# MotorCell.net
KiCad netlist of a schematic drawn in Altium Designer
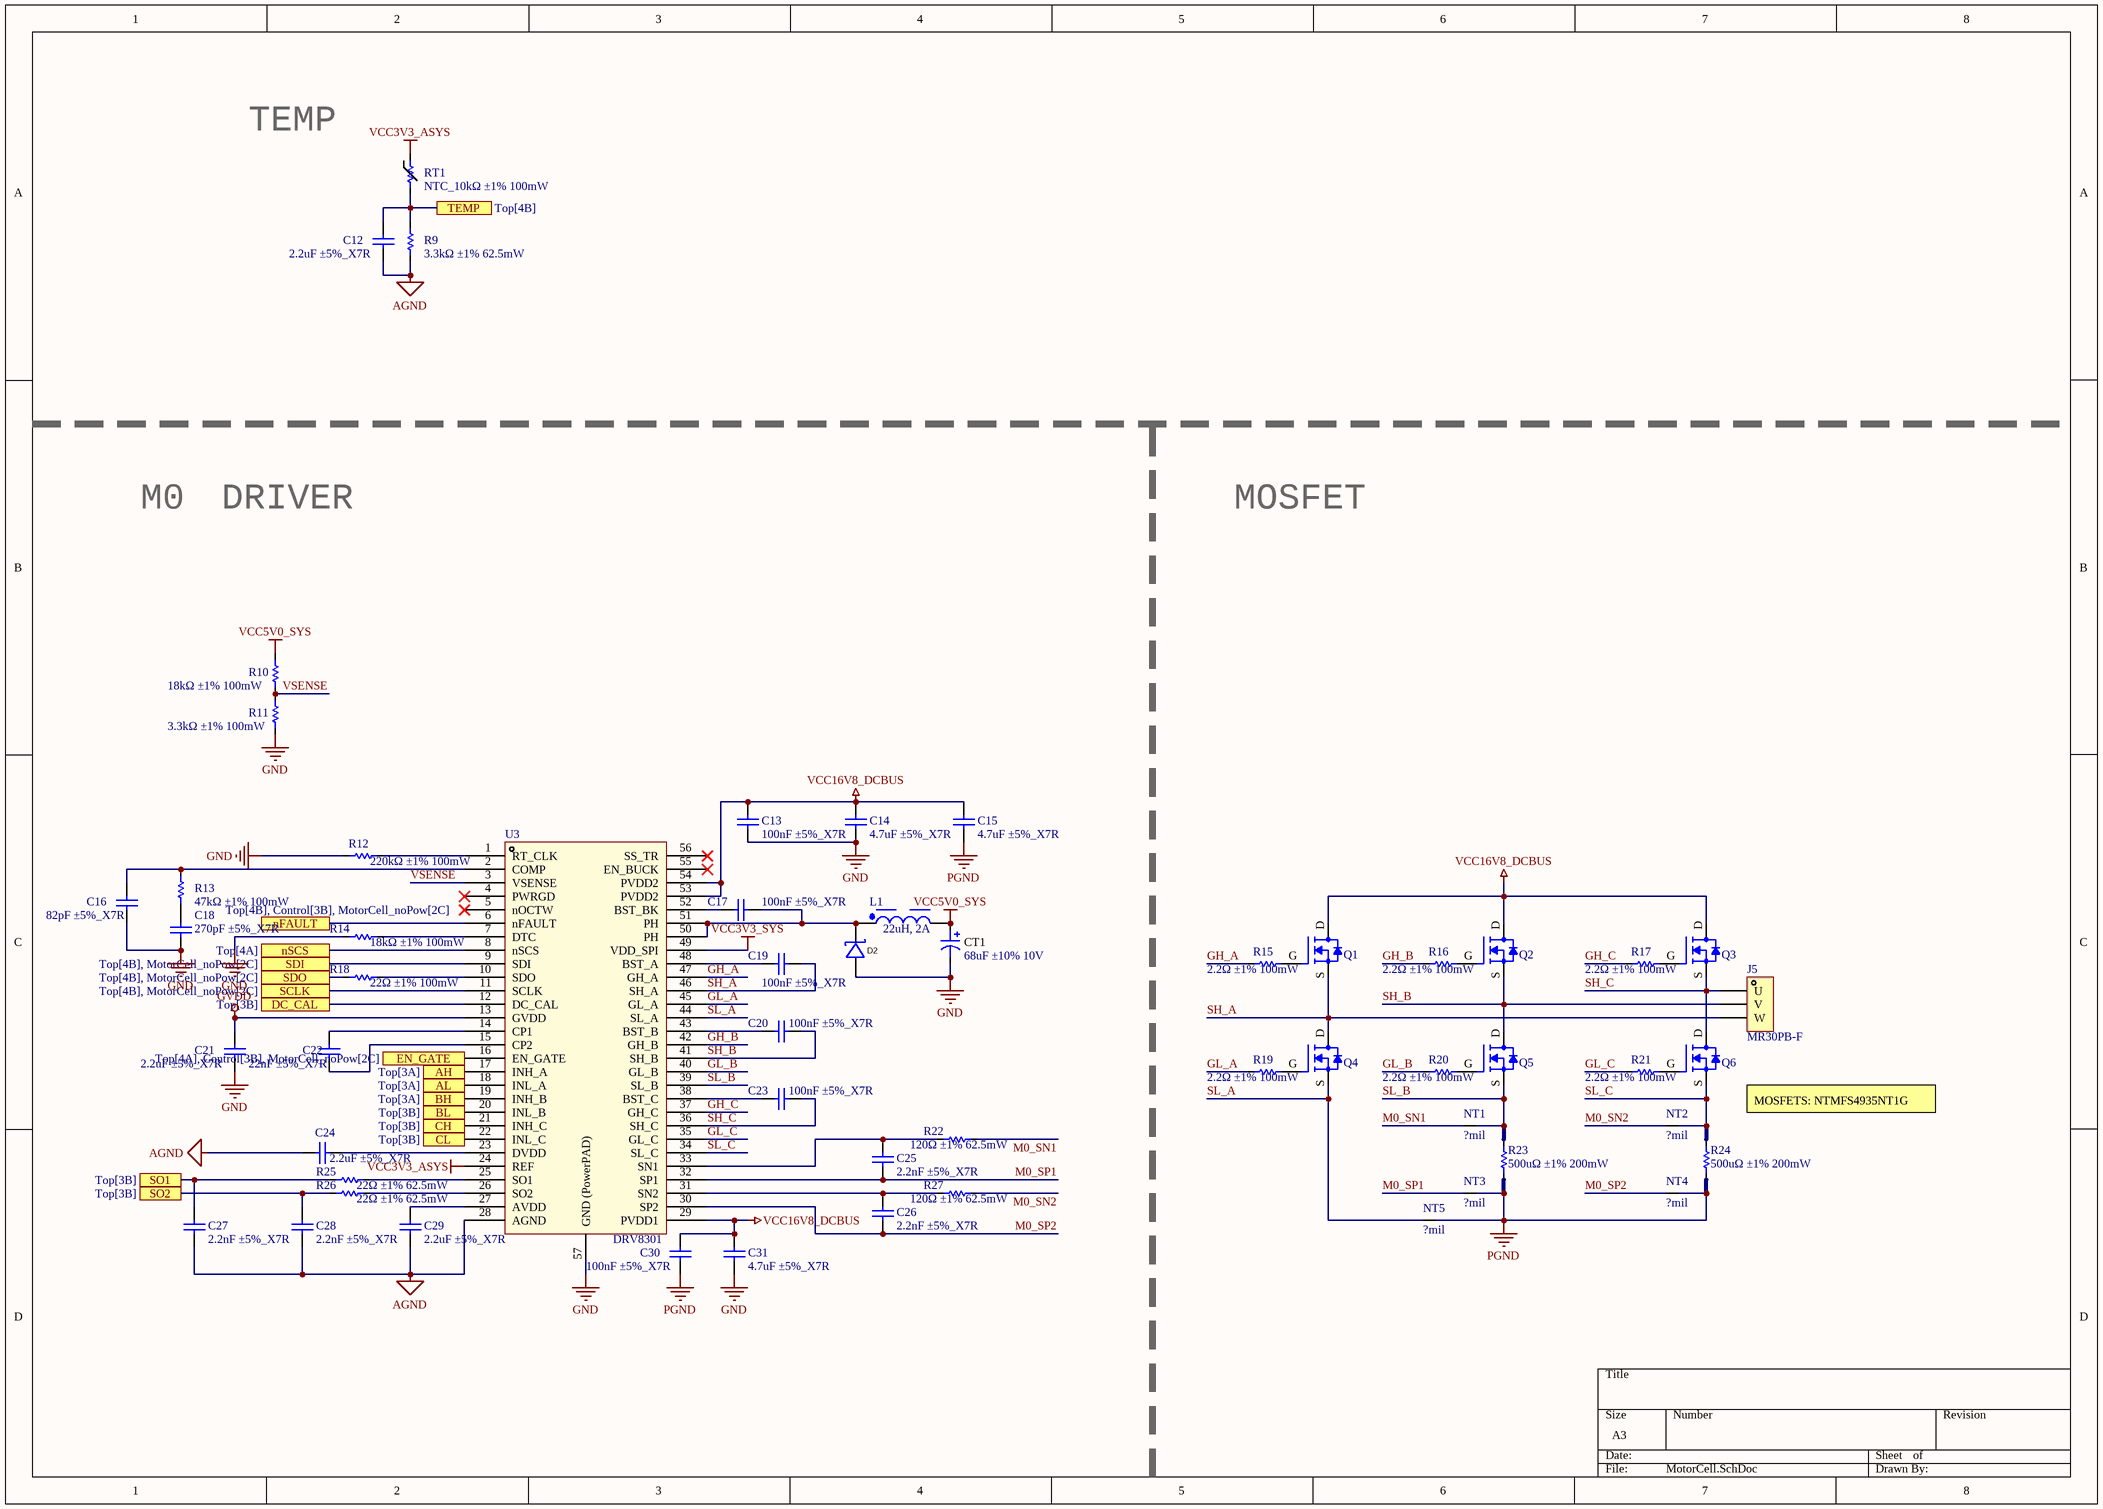
[diagram p0: MotorCell.SchDoc]

(export (version "E")
  (design (tool "Eeschema 10.0.6"))
  (components
    (comp (ref "C12")
      (value "2.2uF ±5%_X7R")
      (footprint "C0402")
      (description "Capacitor")
      (fields (field (name "PUBLISHER") "Altium Limited"))
      (libsource (lib "Component") (part "Cap"))
    )
    (comp (ref "C13")
      (value "100nF ±5%_X7R")
      (footprint "C0402")
      (description "Capacitor")
      (fields (field (name "PUBLISHER") "Altium Limited"))
      (libsource (lib "Component") (part "Cap"))
    )
    (comp (ref "C14")
      (value "4.7uF ±5%_X7R")
      (footprint "C0603")
      (description "Capacitor")
      (fields (field (name "PUBLISHER") "Altium Limited"))
      (libsource (lib "Component") (part "Cap"))
    )
    (comp (ref "C15")
      (value "4.7uF ±5%_X7R")
      (footprint "C0603")
      (description "Capacitor")
      (fields (field (name "PUBLISHER") "Altium Limited"))
      (libsource (lib "Component") (part "Cap"))
    )
    (comp (ref "C16")
      (value "82pF ±5%_X7R")
      (footprint "C0402")
      (description "Capacitor")
      (fields (field (name "PUBLISHER") "Altium Limited"))
      (libsource (lib "Component") (part "Cap"))
    )
    (comp (ref "C17")
      (value "100nF ±5%_X7R")
      (footprint "C0402")
      (description "Capacitor")
      (fields (field (name "PUBLISHER") "Altium Limited"))
      (libsource (lib "Component") (part "Cap"))
    )
    (comp (ref "C18")
      (value "270pF ±5%_X7R")
      (footprint "C0402")
      (description "Capacitor")
      (fields (field (name "PUBLISHER") "Altium Limited"))
      (libsource (lib "Component") (part "Cap"))
    )
    (comp (ref "C19")
      (value "100nF ±5%_X7R")
      (footprint "C0402")
      (description "Capacitor")
      (fields (field (name "PUBLISHER") "Altium Limited"))
      (libsource (lib "Component") (part "Cap"))
    )
    (comp (ref "C20")
      (value "100nF ±5%_X7R")
      (footprint "C0402")
      (description "Capacitor")
      (fields (field (name "PUBLISHER") "Altium Limited"))
      (libsource (lib "Component") (part "Cap"))
    )
    (comp (ref "C21")
      (value "2.2uF ±5%_X7R")
      (footprint "C0603")
      (description "Capacitor")
      (fields (field (name "PUBLISHER") "Altium Limited"))
      (libsource (lib "Component") (part "Cap"))
    )
    (comp (ref "C22")
      (value "22nF ±5%_X7R")
      (footprint "C0603")
      (description "Capacitor")
      (fields (field (name "PUBLISHER") "Altium Limited"))
      (libsource (lib "Component") (part "Cap"))
    )
    (comp (ref "C23")
      (value "100nF ±5%_X7R")
      (footprint "C0402")
      (description "Capacitor")
      (fields (field (name "PUBLISHER") "Altium Limited"))
      (libsource (lib "Component") (part "Cap"))
    )
    (comp (ref "C24")
      (value "2.2uF ±5%_X7R")
      (footprint "C0603")
      (description "Capacitor")
      (fields (field (name "PUBLISHER") "Altium Limited"))
      (libsource (lib "Component") (part "Cap"))
    )
    (comp (ref "C25")
      (value "2.2nF ±5%_X7R")
      (footprint "C0402")
      (description "Capacitor")
      (fields (field (name "PUBLISHER") "Altium Limited"))
      (libsource (lib "Component") (part "Cap"))
    )
    (comp (ref "C26")
      (value "2.2nF ±5%_X7R")
      (footprint "C0402")
      (description "Capacitor")
      (fields (field (name "PUBLISHER") "Altium Limited"))
      (libsource (lib "Component") (part "Cap"))
    )
    (comp (ref "C27")
      (value "2.2nF ±5%_X7R")
      (footprint "C0402")
      (description "Capacitor")
      (fields (field (name "PUBLISHER") "Altium Limited"))
      (libsource (lib "Component") (part "Cap"))
    )
    (comp (ref "C28")
      (value "2.2nF ±5%_X7R")
      (footprint "C0402")
      (description "Capacitor")
      (fields (field (name "PUBLISHER") "Altium Limited"))
      (libsource (lib "Component") (part "Cap"))
    )
    (comp (ref "C29")
      (value "2.2uF ±5%_X7R")
      (footprint "C0603")
      (description "Capacitor")
      (fields (field (name "PUBLISHER") "Altium Limited"))
      (libsource (lib "Component") (part "Cap"))
    )
    (comp (ref "C30")
      (value "100nF ±5%_X7R")
      (footprint "C0402")
      (description "Capacitor")
      (fields (field (name "PUBLISHER") "Altium Limited"))
      (libsource (lib "Component") (part "Cap"))
    )
    (comp (ref "C31")
      (value "4.7uF ±5%_X7R")
      (footprint "C0603")
      (description "Capacitor")
      (fields (field (name "PUBLISHER") "Altium Limited"))
      (libsource (lib "Component") (part "Cap"))
    )
    (comp (ref "CT1")
      (value "68uF ±10% 10V")
      (footprint "CAP-SMD-R-RD")
      (description "容值:330uF;精度:±20%;额定电压:6.3V;等效串联电阻:-;")
      (fields (field (name "MANUFACTURER") "湘怡中元/湘江") (field (name "MANUFACTURER PART") "CA45-C6R3M337T"))
      (libsource (lib "Component") (part "Cap TANT"))
    )
    (comp (ref "D2")
      (value "B340A-13-F")
      (footprint "SMA_L4.4-W2.6-LS5.0-RD")
      (description "直流反向耐压(Vr):40V;平均整流电流(Io):3A;正向压降(Vf):500mV@3A;")
      (fields (field (name "MANUFACTURER") "DIODES(美台)"))
      (libsource (lib "Component") (part "Diode_Schottky"))
    )
    (comp (ref "J5")
      (value "MR30PB-F")
      (footprint "MR30PB-F [Straight] [SMT]")
      (description "驱动器端")
      (libsource (lib "Connectivity_Plugs") (part "MR30PB-F [Straight] [SMT]"))
    )
    (comp (ref "L1")
      (value "22uH, 2A")
      (footprint "WE-PD_6050R")
      (description "WE-PD SMT Power Inductor, size 6050R, 22uH, 2A, 115mOhm")
      (fields
        (field (name "MANUFACTURER PART NUMBER") "7447786122")
        (field (name "MANUFACTURER") "Wurth Elektronik")
      )
      (libsource (lib "WE-PD (rev22g)") (part "7447786122"))
    )
    (comp (ref "NT1") (value "?mil") (footprint "NETTIE_8mil") (libsource (lib "Component") (part "NETTIE")))
    (comp (ref "NT2") (value "?mil") (footprint "NETTIE_8mil") (libsource (lib "Component") (part "NETTIE")))
    (comp (ref "NT3") (value "?mil") (footprint "NETTIE_8mil") (libsource (lib "Component") (part "NETTIE")))
    (comp (ref "NT4") (value "?mil") (footprint "NETTIE_8mil") (libsource (lib "Component") (part "NETTIE")))
    (comp (ref "NT5") (value "?mil") (footprint "NETTIE_8mil") (libsource (lib "Component") (part "NETTIE")))
    (comp (ref "Q1")
      (value "NTMFS4935NT1G")
      (footprint "NRVTS10100EMFST1G")
      (description "MOSFET – Power, Single,\r\nN-Channel, SO-8 FL\r\n30 V, 93 A")
      (fields (field (name "MANUFACTURER") "ON Semiconductor"))
      (libsource (lib "Component") (part "MOSFET-N"))
    )
    (comp (ref "Q2")
      (value "NTMFS4935NT1G")
      (footprint "NRVTS10100EMFST1G")
      (description "MOSFET – Power, Single,\r\nN-Channel, SO-8 FL\r\n30 V, 93 A")
      (fields (field (name "MANUFACTURER") "ON Semiconductor"))
      (libsource (lib "Component") (part "MOSFET-N"))
    )
    (comp (ref "Q3")
      (value "NTMFS4935NT1G")
      (footprint "NRVTS10100EMFST1G")
      (description "MOSFET – Power, Single,\r\nN-Channel, SO-8 FL\r\n30 V, 93 A")
      (fields (field (name "MANUFACTURER") "ON Semiconductor"))
      (libsource (lib "Component") (part "MOSFET-N"))
    )
    (comp (ref "Q4")
      (value "NTMFS4935NT1G")
      (footprint "NRVTS10100EMFST1G")
      (description "MOSFET – Power, Single,\r\nN-Channel, SO-8 FL\r\n30 V, 93 A")
      (fields (field (name "MANUFACTURER") "ON Semiconductor"))
      (libsource (lib "Component") (part "MOSFET-N"))
    )
    (comp (ref "Q5")
      (value "NTMFS4935NT1G")
      (footprint "NRVTS10100EMFST1G")
      (description "MOSFET – Power, Single,\r\nN-Channel, SO-8 FL\r\n30 V, 93 A")
      (fields (field (name "MANUFACTURER") "ON Semiconductor"))
      (libsource (lib "Component") (part "MOSFET-N"))
    )
    (comp (ref "Q6")
      (value "NTMFS4935NT1G")
      (footprint "NRVTS10100EMFST1G")
      (description "MOSFET – Power, Single,\r\nN-Channel, SO-8 FL\r\n30 V, 93 A")
      (fields (field (name "MANUFACTURER") "ON Semiconductor"))
      (libsource (lib "Component") (part "MOSFET-N"))
    )
    (comp (ref "R9")
      (value "3.3kΩ ±1% 62.5mW")
      (footprint "R0402")
      (description "Resistor")
      (fields (field (name "PUBLISHER") "Altium Limited"))
      (libsource (lib "Component") (part "Res"))
    )
    (comp (ref "R10")
      (value "18kΩ ±1% 100mW")
      (footprint "R0402")
      (description "Resistor")
      (fields (field (name "PUBLISHER") "Altium Limited"))
      (libsource (lib "Component") (part "Res"))
    )
    (comp (ref "R11")
      (value "3.3kΩ ±1% 100mW")
      (footprint "R0402")
      (description "Resistor")
      (fields (field (name "PUBLISHER") "Altium Limited"))
      (libsource (lib "Component") (part "Res"))
    )
    (comp (ref "R12")
      (value "220kΩ ±1% 100mW")
      (footprint "R0402")
      (description "Resistor")
      (fields (field (name "PUBLISHER") "Altium Limited"))
      (libsource (lib "Component") (part "Res"))
    )
    (comp (ref "R13")
      (value "47kΩ ±1% 100mW")
      (footprint "R0402")
      (description "Resistor")
      (fields (field (name "PUBLISHER") "Altium Limited"))
      (libsource (lib "Component") (part "Res"))
    )
    (comp (ref "R14")
      (value "18kΩ ±1% 100mW")
      (footprint "R0402")
      (description "Resistor")
      (fields (field (name "PUBLISHER") "Altium Limited"))
      (libsource (lib "Component") (part "Res"))
    )
    (comp (ref "R15")
      (value "2.2Ω ±1% 100mW")
      (footprint "R0402")
      (description "Resistor")
      (fields (field (name "PUBLISHER") "Altium Limited"))
      (libsource (lib "Component") (part "Res"))
    )
    (comp (ref "R16")
      (value "2.2Ω ±1% 100mW")
      (footprint "R0402")
      (description "Resistor")
      (fields (field (name "PUBLISHER") "Altium Limited"))
      (libsource (lib "Component") (part "Res"))
    )
    (comp (ref "R17")
      (value "2.2Ω ±1% 100mW")
      (footprint "R0402")
      (description "Resistor")
      (fields (field (name "PUBLISHER") "Altium Limited"))
      (libsource (lib "Component") (part "Res"))
    )
    (comp (ref "R18")
      (value "22Ω ±1% 100mW")
      (footprint "R0402")
      (description "Resistor")
      (fields (field (name "PUBLISHER") "Altium Limited"))
      (libsource (lib "Component") (part "Res"))
    )
    (comp (ref "R19")
      (value "2.2Ω ±1% 100mW")
      (footprint "R0402")
      (description "Resistor")
      (fields (field (name "PUBLISHER") "Altium Limited"))
      (libsource (lib "Component") (part "Res"))
    )
    (comp (ref "R20")
      (value "2.2Ω ±1% 100mW")
      (footprint "R0402")
      (description "Resistor")
      (fields (field (name "PUBLISHER") "Altium Limited"))
      (libsource (lib "Component") (part "Res"))
    )
    (comp (ref "R21")
      (value "2.2Ω ±1% 100mW")
      (footprint "R0402")
      (description "Resistor")
      (fields (field (name "PUBLISHER") "Altium Limited"))
      (libsource (lib "Component") (part "Res"))
    )
    (comp (ref "R22")
      (value "120Ω ±1% 62.5mW")
      (footprint "R0402")
      (description "Resistor")
      (fields (field (name "PUBLISHER") "Altium Limited"))
      (libsource (lib "Component") (part "Res"))
    )
    (comp (ref "R23")
      (value "500uΩ ±1% 200mW")
      (footprint "R2512")
      (description "Resistor")
      (fields (field (name "PUBLISHER") "Altium Limited"))
      (libsource (lib "Component") (part "Res"))
    )
    (comp (ref "R24")
      (value "500uΩ ±1% 200mW")
      (footprint "R2512")
      (description "Resistor")
      (fields (field (name "PUBLISHER") "Altium Limited"))
      (libsource (lib "Component") (part "Res"))
    )
    (comp (ref "R25")
      (value "22Ω ±1% 62.5mW")
      (footprint "R0402")
      (description "Resistor")
      (fields (field (name "PUBLISHER") "Altium Limited"))
      (libsource (lib "Component") (part "Res"))
    )
    (comp (ref "R26")
      (value "22Ω ±1% 62.5mW")
      (footprint "R0402")
      (description "Resistor")
      (fields (field (name "PUBLISHER") "Altium Limited"))
      (libsource (lib "Component") (part "Res"))
    )
    (comp (ref "R27")
      (value "120Ω ±1% 62.5mW")
      (footprint "R0402")
      (description "Resistor")
      (fields (field (name "PUBLISHER") "Altium Limited"))
      (libsource (lib "Component") (part "Res"))
    )
    (comp (ref "RT1")
      (value "NTC_10kΩ ±1% 100mW")
      (footprint "R0402")
      (description "THERMISTOR 10K OHM NTC 0402 SMD")
      (libsource (lib "Component") (part "TEMP RES"))
    )
    (comp (ref "U3")
      (value "DRV8301")
      (footprint "TSSOP50P810X120_HS-57N")
      (description "MOTOR DRIVER, 3PH, 56HTSSOP")
      (libsource (lib "IC") (part "DRV8301"))
    )
  )
  (nets
    (net (code "1") (name "/AH") (class "Default")
      (node (ref "U3") (pin "17") (pinfunction "INH_A_17") (pintype "passive"))
    )
    (net (code "2") (name "/AL") (class "Default")
      (node (ref "U3") (pin "18") (pinfunction "INL_A_18") (pintype "passive"))
    )
    (net (code "3") (name "/BH") (class "Default")
      (node (ref "U3") (pin "19") (pinfunction "INH_B_19") (pintype "passive"))
    )
    (net (code "4") (name "/BL") (class "Default")
      (node (ref "U3") (pin "20") (pinfunction "INL_B_20") (pintype "passive"))
    )
    (net (code "5") (name "/CH") (class "Default")
      (node (ref "U3") (pin "21") (pinfunction "INH_C_21") (pintype "passive"))
    )
    (net (code "6") (name "/CL") (class "Default")
      (node (ref "U3") (pin "22") (pinfunction "INL_C_22") (pintype "passive"))
    )
    (net (code "7") (name "/DC_CAL") (class "Default")
      (node (ref "U3") (pin "12") (pinfunction "DC_CAL_12") (pintype "passive"))
    )
    (net (code "8") (name "/EN_GATE") (class "Default")
      (node (ref "U3") (pin "16") (pinfunction "EN_GATE_16") (pintype "passive"))
    )
    (net (code "9") (name "/GH_A") (class "Default")
      (node (ref "R15") (pin "1") (pinfunction "1_1") (pintype "passive"))
      (node (ref "U3") (pin "47") (pinfunction "GH_A_47") (pintype "passive"))
    )
    (net (code "10") (name "/GH_B") (class "Default")
      (node (ref "R16") (pin "1") (pinfunction "1_1") (pintype "passive"))
      (node (ref "U3") (pin "42") (pinfunction "GH_B_42") (pintype "passive"))
    )
    (net (code "11") (name "/GH_C") (class "Default")
      (node (ref "R17") (pin "1") (pinfunction "1_1") (pintype "passive"))
      (node (ref "U3") (pin "37") (pinfunction "GH_C_37") (pintype "passive"))
    )
    (net (code "12") (name "/GL_A") (class "Default")
      (node (ref "R19") (pin "1") (pinfunction "1_1") (pintype "passive"))
      (node (ref "U3") (pin "45") (pinfunction "GL_A_45") (pintype "passive"))
    )
    (net (code "13") (name "/GL_B") (class "Default")
      (node (ref "R20") (pin "1") (pinfunction "1_1") (pintype "passive"))
      (node (ref "U3") (pin "40") (pinfunction "GL_B_40") (pintype "passive"))
    )
    (net (code "14") (name "/GL_C") (class "Default")
      (node (ref "R21") (pin "1") (pinfunction "1_1") (pintype "passive"))
      (node (ref "U3") (pin "35") (pinfunction "GL_C_35") (pintype "passive"))
    )
    (net (code "15") (name "/M0_SN1") (class "Default")
      (node (ref "NT1") (pin "1") (pinfunction "1_1") (pintype "passive"))
      (node (ref "R22") (pin "1") (pinfunction "1_1") (pintype "passive"))
    )
    (net (code "16") (name "/M0_SN2") (class "Default")
      (node (ref "NT2") (pin "1") (pinfunction "1_1") (pintype "passive"))
      (node (ref "R27") (pin "1") (pinfunction "1_1") (pintype "passive"))
    )
    (net (code "17") (name "/M0_SP1") (class "Default")
      (node (ref "C25") (pin "1") (pinfunction "1_1") (pintype "passive"))
      (node (ref "NT3") (pin "1") (pinfunction "1_1") (pintype "passive"))
      (node (ref "U3") (pin "32") (pinfunction "SP1_32") (pintype "passive"))
    )
    (net (code "18") (name "/M0_SP2") (class "Default")
      (node (ref "C26") (pin "1") (pinfunction "1_1") (pintype "passive"))
      (node (ref "NT4") (pin "1") (pinfunction "1_1") (pintype "passive"))
      (node (ref "U3") (pin "30") (pinfunction "SP2_30") (pintype "passive"))
    )
    (net (code "19") (name "/SCLK") (class "Default")
      (node (ref "U3") (pin "11") (pinfunction "SCLK_11") (pintype "passive"))
    )
    (net (code "20") (name "/SDI") (class "Default")
      (node (ref "U3") (pin "9") (pinfunction "SDI_9") (pintype "passive"))
    )
    (net (code "21") (name "/SDO") (class "Default")
      (node (ref "R18") (pin "1") (pinfunction "1_1") (pintype "passive"))
    )
    (net (code "22") (name "/SH_A") (class "Default")
      (node (ref "C19") (pin "1") (pinfunction "1_1") (pintype "passive"))
      (node (ref "J5") (pin "3") (pinfunction "W_3") (pintype "passive"))
      (node (ref "Q1") (pin "S") (pinfunction "S_S") (pintype "passive"))
      (node (ref "Q4") (pin "D") (pinfunction "D_D") (pintype "passive"))
      (node (ref "U3") (pin "46") (pinfunction "SH_A_46") (pintype "passive"))
    )
    (net (code "23") (name "/SH_B") (class "Default")
      (node (ref "C20") (pin "1") (pinfunction "1_1") (pintype "passive"))
      (node (ref "J5") (pin "2") (pinfunction "V_2") (pintype "passive"))
      (node (ref "Q2") (pin "S") (pinfunction "S_S") (pintype "passive"))
      (node (ref "Q5") (pin "D") (pinfunction "D_D") (pintype "passive"))
      (node (ref "U3") (pin "41") (pinfunction "SH_B_41") (pintype "passive"))
    )
    (net (code "24") (name "/SH_C") (class "Default")
      (node (ref "C23") (pin "1") (pinfunction "1_1") (pintype "passive"))
      (node (ref "J5") (pin "1") (pinfunction "U_1") (pintype "passive"))
      (node (ref "Q3") (pin "S") (pinfunction "S_S") (pintype "passive"))
      (node (ref "Q6") (pin "D") (pinfunction "D_D") (pintype "passive"))
      (node (ref "U3") (pin "36") (pinfunction "SH_C_36") (pintype "passive"))
    )
    (net (code "25") (name "/SL_A") (class "Default")
      (node (ref "NT5") (pin "1") (pinfunction "1_1") (pintype "passive"))
      (node (ref "Q4") (pin "S") (pinfunction "S_S") (pintype "passive"))
      (node (ref "U3") (pin "44") (pinfunction "SL_A_44") (pintype "passive"))
    )
    (net (code "26") (name "/SL_B") (class "Default")
      (node (ref "NT1") (pin "2") (pinfunction "2_2") (pintype "passive"))
      (node (ref "Q5") (pin "S") (pinfunction "S_S") (pintype "passive"))
      (node (ref "R23") (pin "2") (pinfunction "2_2") (pintype "passive"))
      (node (ref "U3") (pin "39") (pinfunction "SL_B_39") (pintype "passive"))
    )
    (net (code "27") (name "/SL_C") (class "Default")
      (node (ref "NT2") (pin "2") (pinfunction "2_2") (pintype "passive"))
      (node (ref "Q6") (pin "S") (pinfunction "S_S") (pintype "passive"))
      (node (ref "R24") (pin "2") (pinfunction "2_2") (pintype "passive"))
      (node (ref "U3") (pin "34") (pinfunction "SL_C_34") (pintype "passive"))
    )
    (net (code "28") (name "/SO1") (class "Default")
      (node (ref "C27") (pin "2") (pinfunction "2_2") (pintype "passive"))
      (node (ref "R25") (pin "2") (pinfunction "2_2") (pintype "passive"))
    )
    (net (code "29") (name "/SO2") (class "Default")
      (node (ref "C28") (pin "2") (pinfunction "2_2") (pintype "passive"))
      (node (ref "R26") (pin "2") (pinfunction "2_2") (pintype "passive"))
    )
    (net (code "30") (name "/TEMP") (class "Default")
      (node (ref "C12") (pin "2") (pinfunction "2_2") (pintype "passive"))
      (node (ref "R9") (pin "1") (pinfunction "1_1") (pintype "passive"))
      (node (ref "RT1") (pin "2") (pinfunction "2_2") (pintype "passive"))
    )
    (net (code "31") (name "/VSENSE") (class "Default")
      (node (ref "R10") (pin "1") (pinfunction "1_1") (pintype "passive"))
      (node (ref "R11") (pin "2") (pinfunction "2_2") (pintype "passive"))
      (node (ref "U3") (pin "3") (pinfunction "VSENSE_3") (pintype "passive"))
    )
    (net (code "32") (name "/nFAULT") (class "Default")
      (node (ref "U3") (pin "6") (pinfunction "nFAULT_6") (pintype "passive"))
    )
    (net (code "33") (name "/nSCS") (class "Default")
      (node (ref "U3") (pin "8") (pinfunction "nSCS_8") (pintype "passive"))
    )
    (net (code "34") (name "AGND") (class "Default")
      (node (ref "C12") (pin "1") (pinfunction "1_1") (pintype "passive"))
      (node (ref "C24") (pin "2") (pinfunction "2_2") (pintype "passive"))
      (node (ref "C27") (pin "1") (pinfunction "1_1") (pintype "passive"))
      (node (ref "C28") (pin "1") (pinfunction "1_1") (pintype "passive"))
      (node (ref "C29") (pin "1") (pinfunction "1_1") (pintype "passive"))
      (node (ref "R9") (pin "2") (pinfunction "2_2") (pintype "passive"))
      (node (ref "U3") (pin "28") (pinfunction "AGND_28") (pintype "passive"))
    )
    (net (code "35") (name "GND") (class "Default")
      (node (ref "C13") (pin "1") (pinfunction "1_1") (pintype "passive"))
      (node (ref "C14") (pin "1") (pinfunction "1_1") (pintype "passive"))
      (node (ref "C16") (pin "1") (pinfunction "1_1") (pintype "passive"))
      (node (ref "C18") (pin "1") (pinfunction "1_1") (pintype "passive"))
      (node (ref "C21") (pin "1") (pinfunction "1_1") (pintype "passive"))
      (node (ref "C31") (pin "1") (pinfunction "1_1") (pintype "passive"))
      (node (ref "CT1") (pin "2") (pinfunction "2_2") (pintype "passive"))
      (node (ref "D2") (pin "2") (pinfunction "A_2") (pintype "passive"))
      (node (ref "R11") (pin "1") (pinfunction "1_1") (pintype "passive"))
      (node (ref "R12") (pin "2") (pinfunction "2_2") (pintype "passive"))
      (node (ref "R14") (pin "2") (pinfunction "2_2") (pintype "passive"))
      (node (ref "U3") (pin "57") (pinfunction "GND_(PowerPAD)_57") (pintype "passive"))
    )
    (net (code "36") (name "GVDD") (class "Default")
      (node (ref "C21") (pin "2") (pinfunction "2_2") (pintype "passive"))
      (node (ref "U3") (pin "13") (pinfunction "GVDD_13") (pintype "passive"))
    )
    (net (code "37") (name "Net-(C18-Pad2)") (class "Default")
      (node (ref "C18") (pin "2") (pinfunction "2_2") (pintype "passive"))
      (node (ref "R13") (pin "1") (pinfunction "1_1") (pintype "passive"))
    )
    (net (code "38") (name "Net-(D2-K)") (class "Default")
      (node (ref "C17") (pin "1") (pinfunction "1_1") (pintype "passive"))
      (node (ref "D2") (pin "1") (pinfunction "K_1") (pintype "passive"))
      (node (ref "L1") (pin "1") (pinfunction "1_1") (pintype "passive"))
      (node (ref "U3") (pin "50") (pinfunction "PH_50") (pintype "passive"))
      (node (ref "U3") (pin "51") (pinfunction "PH_51") (pintype "passive"))
    )
    (net (code "39") (name "Net-(Q1-PadG)") (class "Default")
      (node (ref "Q1") (pin "G") (pinfunction "G_G") (pintype "passive"))
      (node (ref "R15") (pin "2") (pinfunction "2_2") (pintype "passive"))
    )
    (net (code "40") (name "Net-(Q2-PadG)") (class "Default")
      (node (ref "Q2") (pin "G") (pinfunction "G_G") (pintype "passive"))
      (node (ref "R16") (pin "2") (pinfunction "2_2") (pintype "passive"))
    )
    (net (code "41") (name "Net-(Q3-PadG)") (class "Default")
      (node (ref "Q3") (pin "G") (pinfunction "G_G") (pintype "passive"))
      (node (ref "R17") (pin "2") (pinfunction "2_2") (pintype "passive"))
    )
    (net (code "42") (name "Net-(Q4-PadG)") (class "Default")
      (node (ref "Q4") (pin "G") (pinfunction "G_G") (pintype "passive"))
      (node (ref "R19") (pin "2") (pinfunction "2_2") (pintype "passive"))
    )
    (net (code "43") (name "Net-(Q5-PadG)") (class "Default")
      (node (ref "Q5") (pin "G") (pinfunction "G_G") (pintype "passive"))
      (node (ref "R20") (pin "2") (pinfunction "2_2") (pintype "passive"))
    )
    (net (code "44") (name "Net-(Q6-PadG)") (class "Default")
      (node (ref "Q6") (pin "G") (pinfunction "G_G") (pintype "passive"))
      (node (ref "R21") (pin "2") (pinfunction "2_2") (pintype "passive"))
    )
    (net (code "45") (name "Net-(U3-AVDD)") (class "Default")
      (node (ref "C29") (pin "2") (pinfunction "2_2") (pintype "passive"))
      (node (ref "U3") (pin "27") (pinfunction "AVDD_27") (pintype "passive"))
    )
    (net (code "46") (name "Net-(U3-BST_A)") (class "Default")
      (node (ref "C19") (pin "2") (pinfunction "2_2") (pintype "passive"))
      (node (ref "U3") (pin "48") (pinfunction "BST_A_48") (pintype "passive"))
    )
    (net (code "47") (name "Net-(U3-BST_B)") (class "Default")
      (node (ref "C20") (pin "2") (pinfunction "2_2") (pintype "passive"))
      (node (ref "U3") (pin "43") (pinfunction "BST_B_43") (pintype "passive"))
    )
    (net (code "48") (name "Net-(U3-BST_BK)") (class "Default")
      (node (ref "C17") (pin "2") (pinfunction "2_2") (pintype "passive"))
      (node (ref "U3") (pin "52") (pinfunction "BST_BK_52") (pintype "passive"))
    )
    (net (code "49") (name "Net-(U3-BST_C)") (class "Default")
      (node (ref "C23") (pin "2") (pinfunction "2_2") (pintype "passive"))
      (node (ref "U3") (pin "38") (pinfunction "BST_C_38") (pintype "passive"))
    )
    (net (code "50") (name "Net-(U3-COMP)") (class "Default")
      (node (ref "C16") (pin "2") (pinfunction "2_2") (pintype "passive"))
      (node (ref "R13") (pin "2") (pinfunction "2_2") (pintype "passive"))
      (node (ref "U3") (pin "2") (pinfunction "COMP_2") (pintype "passive"))
    )
    (net (code "51") (name "Net-(U3-CP1)") (class "Default")
      (node (ref "C22") (pin "1") (pinfunction "1_1") (pintype "passive"))
      (node (ref "U3") (pin "14") (pinfunction "CP1_14") (pintype "passive"))
    )
    (net (code "52") (name "Net-(U3-CP2)") (class "Default")
      (node (ref "C22") (pin "2") (pinfunction "2_2") (pintype "passive"))
      (node (ref "U3") (pin "15") (pinfunction "CP2_15") (pintype "passive"))
    )
    (net (code "53") (name "Net-(U3-DTC)") (class "Default")
      (node (ref "R14") (pin "1") (pinfunction "1_1") (pintype "passive"))
      (node (ref "U3") (pin "7") (pinfunction "DTC_7") (pintype "passive"))
    )
    (net (code "54") (name "Net-(U3-DVDD)") (class "Default")
      (node (ref "C24") (pin "1") (pinfunction "1_1") (pintype "passive"))
      (node (ref "U3") (pin "23") (pinfunction "DVDD_23") (pintype "passive"))
    )
    (net (code "55") (name "Net-(U3-RT_CLK)") (class "Default")
      (node (ref "R12") (pin "1") (pinfunction "1_1") (pintype "passive"))
      (node (ref "U3") (pin "1") (pinfunction "RT_CLK_1") (pintype "passive"))
    )
    (net (code "56") (name "Net-(U3-SDO)") (class "Default")
      (node (ref "R18") (pin "2") (pinfunction "2_2") (pintype "passive"))
      (node (ref "U3") (pin "10") (pinfunction "SDO_10") (pintype "passive"))
    )
    (net (code "57") (name "Net-(U3-SN1)") (class "Default")
      (node (ref "C25") (pin "2") (pinfunction "2_2") (pintype "passive"))
      (node (ref "R22") (pin "2") (pinfunction "2_2") (pintype "passive"))
      (node (ref "U3") (pin "33") (pinfunction "SN1_33") (pintype "passive"))
    )
    (net (code "58") (name "Net-(U3-SN2)") (class "Default")
      (node (ref "C26") (pin "2") (pinfunction "2_2") (pintype "passive"))
      (node (ref "R27") (pin "2") (pinfunction "2_2") (pintype "passive"))
      (node (ref "U3") (pin "31") (pinfunction "SN2_31") (pintype "passive"))
    )
    (net (code "59") (name "Net-(U3-SO1)") (class "Default")
      (node (ref "R25") (pin "1") (pinfunction "1_1") (pintype "passive"))
      (node (ref "U3") (pin "25") (pinfunction "SO1_25") (pintype "passive"))
    )
    (net (code "60") (name "Net-(U3-SO2)") (class "Default")
      (node (ref "R26") (pin "1") (pinfunction "1_1") (pintype "passive"))
      (node (ref "U3") (pin "26") (pinfunction "SO2_26") (pintype "passive"))
    )
    (net (code "61") (name "PGND") (class "Default")
      (node (ref "C15") (pin "1") (pinfunction "1_1") (pintype "passive"))
      (node (ref "C30") (pin "1") (pinfunction "1_1") (pintype "passive"))
      (node (ref "NT3") (pin "2") (pinfunction "2_2") (pintype "passive"))
      (node (ref "NT4") (pin "2") (pinfunction "2_2") (pintype "passive"))
      (node (ref "NT5") (pin "2") (pinfunction "2_2") (pintype "passive"))
      (node (ref "R23") (pin "1") (pinfunction "1_1") (pintype "passive"))
      (node (ref "R24") (pin "1") (pinfunction "1_1") (pintype "passive"))
    )
    (net (code "62") (name "VCC3V3_ASYS") (class "Default")
      (node (ref "RT1") (pin "1") (pinfunction "1_1") (pintype "passive"))
      (node (ref "U3") (pin "24") (pinfunction "REF_24") (pintype "passive"))
    )
    (net (code "63") (name "VCC3V3_SYS") (class "Default")
      (node (ref "U3") (pin "49") (pinfunction "VDD_SPI_49") (pintype "passive"))
    )
    (net (code "64") (name "VCC5V0_SYS") (class "Default")
      (node (ref "CT1") (pin "1") (pinfunction "1_1") (pintype "passive"))
      (node (ref "L1") (pin "2") (pinfunction "2_2") (pintype "passive"))
      (node (ref "R10") (pin "2") (pinfunction "2_2") (pintype "passive"))
    )
    (net (code "65") (name "VCC16V8_DCBUS") (class "Default")
      (node (ref "C13") (pin "2") (pinfunction "2_2") (pintype "passive"))
      (node (ref "C14") (pin "2") (pinfunction "2_2") (pintype "passive"))
      (node (ref "C15") (pin "2") (pinfunction "2_2") (pintype "passive"))
      (node (ref "C30") (pin "2") (pinfunction "2_2") (pintype "passive"))
      (node (ref "C31") (pin "2") (pinfunction "2_2") (pintype "passive"))
      (node (ref "Q1") (pin "D") (pinfunction "D_D") (pintype "passive"))
      (node (ref "Q2") (pin "D") (pinfunction "D_D") (pintype "passive"))
      (node (ref "Q3") (pin "D") (pinfunction "D_D") (pintype "passive"))
      (node (ref "U3") (pin "29") (pinfunction "PVDD1_29") (pintype "passive"))
      (node (ref "U3") (pin "53") (pinfunction "PVDD2_53") (pintype "passive"))
      (node (ref "U3") (pin "54") (pinfunction "PVDD2_54") (pintype "passive"))
    )
    (net (code "66") (name "unconnected-(U3-EN_BUCK-Pad55)") (class "Default")
      (node (ref "U3") (pin "55") (pinfunction "EN_BUCK_55") (pintype "passive+no_connect"))
    )
    (net (code "67") (name "unconnected-(U3-PWRGD-Pad4)") (class "Default")
      (node (ref "U3") (pin "4") (pinfunction "PWRGD_4") (pintype "passive+no_connect"))
    )
    (net (code "68") (name "unconnected-(U3-SS_TR-Pad56)") (class "Default")
      (node (ref "U3") (pin "56") (pinfunction "SS_TR_56") (pintype "passive+no_connect"))
    )
    (net (code "69") (name "unconnected-(U3-nOCTW-Pad5)") (class "Default")
      (node (ref "U3") (pin "5") (pinfunction "nOCTW_5") (pintype "passive+no_connect"))
    )
  )
)
